# STM.net
KiCad netlist of a schematic drawn in Altium Designer
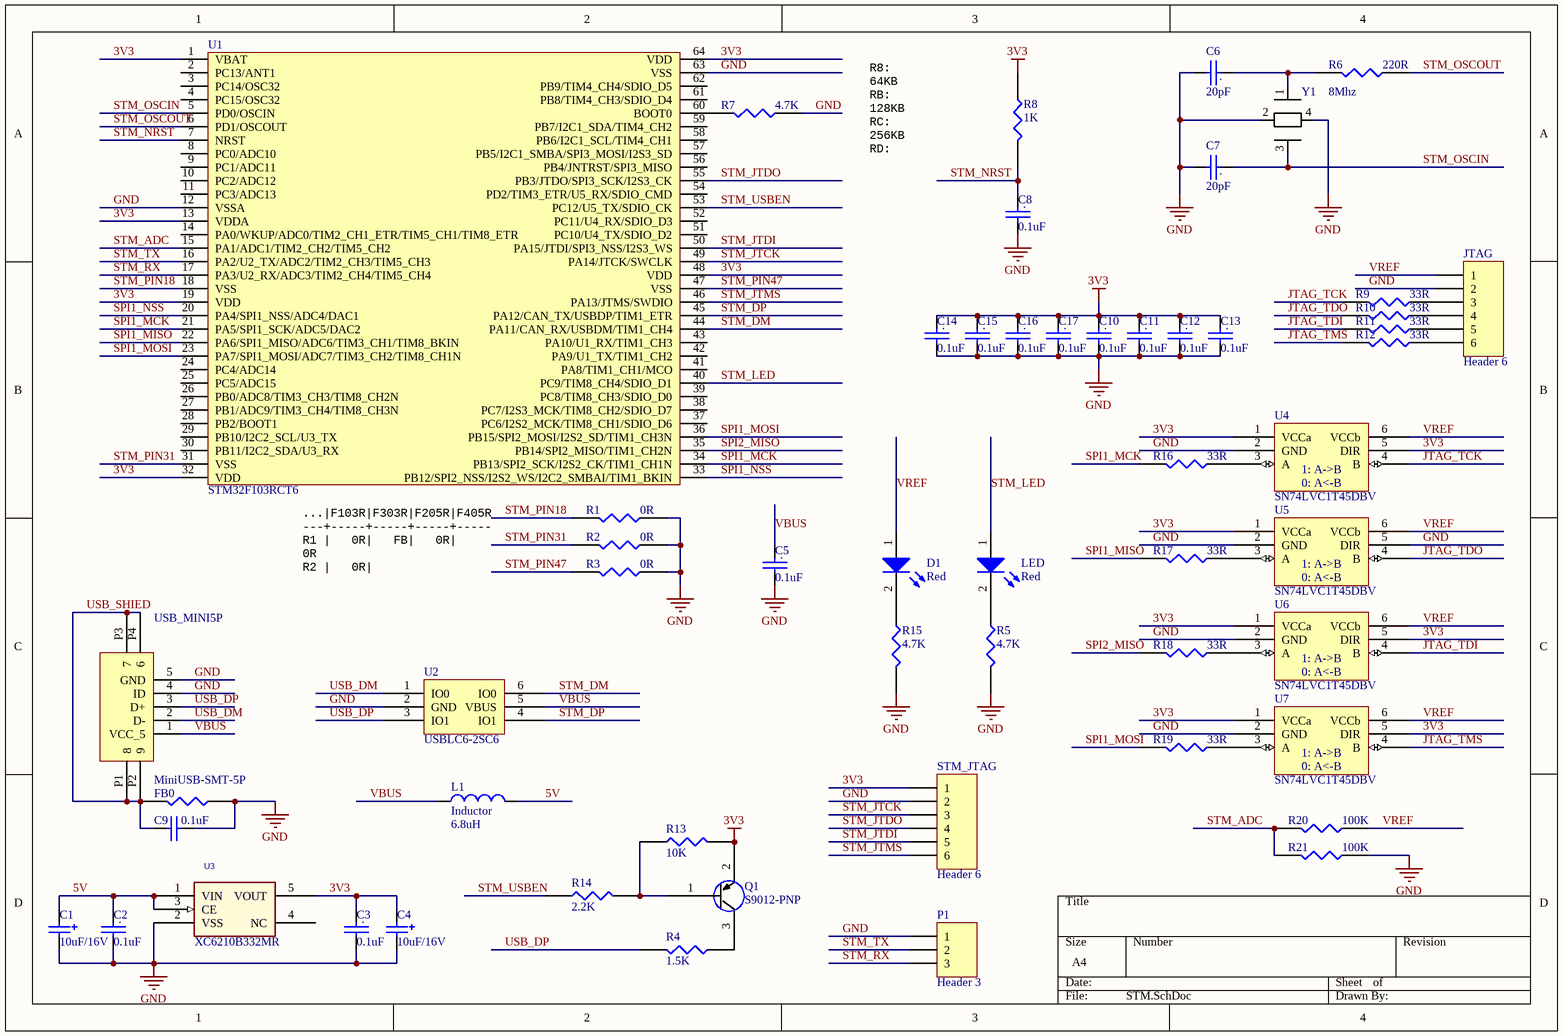
[diagram p0: STM.SchDoc]

(export (version "E")
  (design (tool "Eeschema 10.0.6"))
  (components
    (comp (ref "C1")
      (value "10uF/16V")
      (footprint "C1206")
      (description "Polarized Capacitor (Surface Mount)")
      (fields (field (name "Comment") "CAP") (field (name "PUBLISHER") "Altium Limited"))
      (libsource (lib "R-C-L-D") (part "CAP Polarity"))
    )
    (comp (ref "C2")
      (value "0.1uF")
      (footprint "C0603")
      (description "Capacitor")
      (fields (field (name "Comment") "CAP Ceramics"))
      (libsource (lib "R-C-L-D") (part "CAP Ceramics"))
    )
    (comp (ref "C3")
      (value "0.1uF")
      (footprint "C0603")
      (description "Capacitor")
      (fields (field (name "Comment") "CAP Ceramics"))
      (libsource (lib "R-C-L-D") (part "CAP Ceramics"))
    )
    (comp (ref "C4")
      (value "10uF/16V")
      (footprint "C1206")
      (description "Polarized Capacitor (Surface Mount)")
      (fields (field (name "Comment") "CAP") (field (name "PUBLISHER") "Altium Limited"))
      (libsource (lib "R-C-L-D") (part "CAP Polarity"))
    )
    (comp (ref "C5")
      (value "0.1uF")
      (footprint "C0603")
      (description "Capacitor")
      (fields (field (name "Comment") "CAP Ceramics"))
      (libsource (lib "R-C-L-D") (part "CAP Ceramics"))
    )
    (comp (ref "C6")
      (value "20pF")
      (footprint "C0603")
      (description "Capacitor")
      (fields (field (name "Comment") "CAP Ceramics"))
      (libsource (lib "R-C-L-D") (part "CAP Ceramics"))
    )
    (comp (ref "C7")
      (value "20pF")
      (footprint "C0603")
      (description "Capacitor")
      (fields (field (name "Comment") "CAP Ceramics"))
      (libsource (lib "R-C-L-D") (part "CAP Ceramics"))
    )
    (comp (ref "C8")
      (value "0.1uF")
      (footprint "C0603")
      (description "Capacitor")
      (fields (field (name "Comment") "CAP Ceramics"))
      (libsource (lib "R-C-L-D") (part "CAP Ceramics"))
    )
    (comp (ref "C9")
      (value "0.1uF")
      (footprint "C0603")
      (description "Capacitor")
      (fields (field (name "Comment") "CAP Ceramics"))
      (libsource (lib "R-C-L-D") (part "CAP Ceramics"))
    )
    (comp (ref "C10")
      (value "0.1uF")
      (footprint "C0603")
      (description "Capacitor")
      (fields (field (name "Comment") "CAP Ceramics"))
      (libsource (lib "R-C-L-D") (part "CAP Ceramics"))
    )
    (comp (ref "C11")
      (value "0.1uF")
      (footprint "C0603")
      (description "Capacitor")
      (fields (field (name "Comment") "CAP Ceramics"))
      (libsource (lib "R-C-L-D") (part "CAP Ceramics"))
    )
    (comp (ref "C12")
      (value "0.1uF")
      (footprint "C0603")
      (description "Capacitor")
      (fields (field (name "Comment") "CAP Ceramics"))
      (libsource (lib "R-C-L-D") (part "CAP Ceramics"))
    )
    (comp (ref "C13")
      (value "0.1uF")
      (footprint "C0603")
      (description "Capacitor")
      (fields (field (name "Comment") "CAP Ceramics"))
      (libsource (lib "R-C-L-D") (part "CAP Ceramics"))
    )
    (comp (ref "C14")
      (value "0.1uF")
      (footprint "C0603")
      (description "Capacitor")
      (fields (field (name "Comment") "CAP Ceramics"))
      (libsource (lib "R-C-L-D") (part "CAP Ceramics"))
    )
    (comp (ref "C15")
      (value "0.1uF")
      (footprint "C0603")
      (description "Capacitor")
      (fields (field (name "Comment") "CAP Ceramics"))
      (libsource (lib "R-C-L-D") (part "CAP Ceramics"))
    )
    (comp (ref "C16")
      (value "0.1uF")
      (footprint "C0603")
      (description "Capacitor")
      (fields (field (name "Comment") "CAP Ceramics"))
      (libsource (lib "R-C-L-D") (part "CAP Ceramics"))
    )
    (comp (ref "C17")
      (value "0.1uF")
      (footprint "C0603")
      (description "Capacitor")
      (fields (field (name "Comment") "CAP Ceramics"))
      (libsource (lib "R-C-L-D") (part "CAP Ceramics"))
    )
    (comp (ref "D1")
      (value "Red")
      (footprint "D0603")
      (description "LED")
      (fields (field (name "PUBLISHER") "Altium Limited"))
      (libsource (lib "R-C-L-D") (part "LED"))
    )
    (comp (ref "FB0")
      (value "RES")
      (footprint "R0603")
      (description "Res")
      (libsource (lib "R-C-L-D") (part "RES"))
    )
    (comp (ref "JTAG")
      (value "Header 6")
      (footprint "HDR1X6")
      (description "Header, 6-Pin")
      (fields (field (name "PUBLISHER") "Altium Limited"))
      (libsource (lib "Miscellaneous Connectors") (part "Header 6"))
    )
    (comp (ref "L1")
      (value "Inductor")
      (footprint "L1206")
      (fields (field (name "ALTIUM_VALUE") "6.8uH") (field (name "PUBLISHER") "Altium Limited"))
      (libsource (lib "R-C-L-D") (part "Inductor"))
    )
    (comp (ref "LED")
      (value "Red")
      (footprint "D0603")
      (description "LED")
      (fields (field (name "PUBLISHER") "Altium Limited"))
      (libsource (lib "R-C-L-D") (part "LED"))
    )
    (comp (ref "P1")
      (value "Header 3")
      (footprint "HDR1X3")
      (description "Header, 3-Pin")
      (fields (field (name "PUBLISHER") "Altium Limited"))
      (libsource (lib "Miscellaneous Connectors") (part "Header 3"))
    )
    (comp (ref "Q1")
      (value "S9012-PNP")
      (footprint "SOT23-3")
      (description "S9012-PNP-SOT23")
      (libsource (lib "S9012-PNP-SOT23") (part "S9012"))
    )
    (comp (ref "R1")
      (value "0R")
      (footprint "R0603")
      (description "Res")
      (libsource (lib "R-C-L-D") (part "RES"))
    )
    (comp (ref "R2")
      (value "0R")
      (footprint "R0603")
      (description "Res")
      (libsource (lib "R-C-L-D") (part "RES"))
    )
    (comp (ref "R3")
      (value "0R")
      (footprint "R0603")
      (description "Res")
      (libsource (lib "R-C-L-D") (part "RES"))
    )
    (comp (ref "R4")
      (value "1.5K")
      (footprint "R0603")
      (description "Res")
      (fields (field (name "Comment") "RES"))
      (libsource (lib "R-C-L-D") (part "RES"))
    )
    (comp (ref "R5")
      (value "4.7K")
      (footprint "R0603")
      (description "Res")
      (libsource (lib "R-C-L-D") (part "RES"))
    )
    (comp (ref "R6")
      (value "220R")
      (footprint "R0603")
      (description "Res")
      (libsource (lib "R-C-L-D") (part "RES"))
    )
    (comp (ref "R7")
      (value "4.7K")
      (footprint "R0603")
      (description "Res")
      (libsource (lib "R-C-L-D") (part "RES"))
    )
    (comp (ref "R8")
      (value "1K")
      (footprint "R0603")
      (description "Res")
      (libsource (lib "R-C-L-D") (part "RES"))
    )
    (comp (ref "R9")
      (value "33R")
      (footprint "R0603")
      (description "Res")
      (fields (field (name "Comment") "RES"))
      (libsource (lib "R-C-L-D") (part "RES"))
    )
    (comp (ref "R10")
      (value "33R")
      (footprint "R0603")
      (description "Res")
      (fields (field (name "Comment") "RES"))
      (libsource (lib "R-C-L-D") (part "RES"))
    )
    (comp (ref "R11")
      (value "33R")
      (footprint "R0603")
      (description "Res")
      (fields (field (name "Comment") "RES"))
      (libsource (lib "R-C-L-D") (part "RES"))
    )
    (comp (ref "R12")
      (value "33R")
      (footprint "R0603")
      (description "Res")
      (fields (field (name "Comment") "RES"))
      (libsource (lib "R-C-L-D") (part "RES"))
    )
    (comp (ref "R13")
      (value "10K")
      (footprint "R0603")
      (description "Res")
      (fields (field (name "Comment") "RES"))
      (libsource (lib "R-C-L-D") (part "RES"))
    )
    (comp (ref "R14")
      (value "2.2K")
      (footprint "R0603")
      (description "Res")
      (fields (field (name "Comment") "RES"))
      (libsource (lib "R-C-L-D") (part "RES"))
    )
    (comp (ref "R15")
      (value "4.7K")
      (footprint "R0603")
      (description "Res")
      (libsource (lib "R-C-L-D") (part "RES"))
    )
    (comp (ref "R16")
      (value "33R")
      (footprint "R0603")
      (description "Res")
      (fields (field (name "Comment") "RES"))
      (libsource (lib "R-C-L-D") (part "RES"))
    )
    (comp (ref "R17")
      (value "33R")
      (footprint "R0603")
      (description "Res")
      (fields (field (name "Comment") "RES"))
      (libsource (lib "R-C-L-D") (part "RES"))
    )
    (comp (ref "R18")
      (value "33R")
      (footprint "R0603")
      (description "Res")
      (fields (field (name "Comment") "RES"))
      (libsource (lib "R-C-L-D") (part "RES"))
    )
    (comp (ref "R19")
      (value "33R")
      (footprint "R0603")
      (description "Res")
      (fields (field (name "Comment") "RES"))
      (libsource (lib "R-C-L-D") (part "RES"))
    )
    (comp (ref "R20")
      (value "100K")
      (footprint "R0603")
      (description "Res")
      (libsource (lib "R-C-L-D") (part "RES"))
    )
    (comp (ref "R21")
      (value "100K")
      (footprint "R0603")
      (description "Res")
      (libsource (lib "R-C-L-D") (part "RES"))
    )
    (comp (ref "STM_JTAG")
      (value "Header 6")
      (footprint "HDR1X6")
      (description "Header, 6-Pin")
      (fields (field (name "PUBLISHER") "Altium Limited"))
      (libsource (lib "Miscellaneous Connectors") (part "Header 6"))
    )
    (comp (ref "U1")
      (value "STM32F103RCT6")
      (footprint "LQFP64_DE12_e0.5_PAD1.8x0.3_offset2.3_mm")
      (description "ST STM32 Cortex-M3")
      (libsource (lib "STM32F103R") (part "STM32F103R"))
    )
    (comp (ref "U2")
      (value "USBLC6-2SC6")
      (footprint "SOT23-6")
      (description "USB EMI ESD Protect")
      (libsource (lib "USBLC6-2") (part "USBLC6-2"))
    )
    (comp (ref "U3")
      (value "XC6210B332MR")
      (footprint "SOT23-5")
      (description "5V->3.3V")
      (fields (field (name "Comment") "LDO"))
      (libsource (lib "LDO") (part "XC6210B-3.3"))
    )
    (comp (ref "U4")
      (value "SN74LVC1T45DBV")
      (footprint "SOT23-6")
      (description "TI SN74LVC1T45")
      (libsource (lib "SN74LVC1T45") (part "SN74LVC1T45"))
    )
    (comp (ref "U5")
      (value "SN74LVC1T45DBV")
      (footprint "SOT23-6")
      (description "TI SN74LVC1T45")
      (libsource (lib "SN74LVC1T45") (part "SN74LVC1T45"))
    )
    (comp (ref "U6")
      (value "SN74LVC1T45DBV")
      (footprint "SOT23-6")
      (description "TI SN74LVC1T45")
      (libsource (lib "SN74LVC1T45") (part "SN74LVC1T45"))
    )
    (comp (ref "U7")
      (value "SN74LVC1T45DBV")
      (footprint "SOT23-6")
      (description "TI SN74LVC1T45")
      (libsource (lib "SN74LVC1T45") (part "SN74LVC1T45"))
    )
    (comp (ref "USB_MINI5P")
      (value "MiniUSB-SMT-5P")
      (footprint "USB_MINI")
      (description "MiniUSB SMT")
      (libsource (lib "MiniUSB-5P") (part "MiniUSB_5P"))
    )
    (comp (ref "Y1")
      (value "8Mhz")
      (footprint "SMD3225")
      (description "Crystal")
      (libsource (lib "Crystal") (part "CRY"))
    )
  )
  (nets
    (net (code "1") (name "/5V") (class "Default")
      (node (ref "C1") (pin "1") (pinfunction "1_1") (pintype "passive"))
      (node (ref "C2") (pin "1") (pinfunction "1_1") (pintype "passive"))
      (node (ref "L1") (pin "2") (pinfunction "2_2") (pintype "passive"))
      (node (ref "U3") (pin "1") (pinfunction "VIN_1") (pintype "power_in"))
      (node (ref "U3") (pin "3") (pinfunction "CE_3") (pintype "input"))
    )
    (net (code "2") (name "/JTAG_TCK") (class "Default")
      (node (ref "R9") (pin "2") (pinfunction "2_2") (pintype "passive"))
      (node (ref "U4") (pin "4") (pinfunction "B_4") (pintype "bidirectional"))
    )
    (net (code "3") (name "/JTAG_TDI") (class "Default")
      (node (ref "R11") (pin "2") (pinfunction "2_2") (pintype "passive"))
      (node (ref "U6") (pin "4") (pinfunction "B_4") (pintype "bidirectional"))
    )
    (net (code "4") (name "/JTAG_TDO") (class "Default")
      (node (ref "R10") (pin "2") (pinfunction "2_2") (pintype "passive"))
      (node (ref "U5") (pin "4") (pinfunction "B_4") (pintype "bidirectional"))
    )
    (net (code "5") (name "/JTAG_TMS") (class "Default")
      (node (ref "R12") (pin "2") (pinfunction "2_2") (pintype "passive"))
      (node (ref "U7") (pin "4") (pinfunction "B_4") (pintype "bidirectional"))
    )
    (net (code "6") (name "/SPI1_MCK") (class "Default")
      (node (ref "R16") (pin "2") (pinfunction "2_2") (pintype "passive"))
      (node (ref "U1") (pin "21") (pinfunction "PA5/SPI1_SCK/ADC5/DAC2_21") (pintype "passive"))
      (node (ref "U1") (pin "34") (pinfunction "PB13/SPI2_SCK/I2S2_CK/TIM1_CH1N_34") (pintype "passive"))
    )
    (net (code "7") (name "/SPI1_MISO") (class "Default")
      (node (ref "R17") (pin "2") (pinfunction "2_2") (pintype "passive"))
      (node (ref "U1") (pin "22") (pinfunction "PA6/SPI1_MISO/ADC6/TIM3_CH1/TIM8_BKIN_22") (pintype "passive"))
    )
    (net (code "8") (name "/SPI1_MOSI") (class "Default")
      (node (ref "R19") (pin "2") (pinfunction "2_2") (pintype "passive"))
      (node (ref "U1") (pin "23") (pinfunction "PA7/SPI1_MOSI/ADC7/TIM3_CH2/TIM8_CH1N_23") (pintype "passive"))
      (node (ref "U1") (pin "36") (pinfunction "PB15/SPI2_MOSI/I2S2_SD/TIM1_CH3N_36") (pintype "passive"))
    )
    (net (code "9") (name "/SPI1_NSS") (class "Default")
      (node (ref "U1") (pin "20") (pinfunction "PA4/SPI1_NSS/ADC4/DAC1_20") (pintype "passive"))
      (node (ref "U1") (pin "33") (pinfunction "PB12/SPI2_NSS/I2S2_WS/I2C2_SMBAI/TIM1_BKIN_33") (pintype "passive"))
    )
    (net (code "10") (name "/SPI2_MISO") (class "Default")
      (node (ref "R18") (pin "2") (pinfunction "2_2") (pintype "passive"))
      (node (ref "U1") (pin "35") (pinfunction "PB14/SPI2_MISO/TIM1_CH2N_35") (pintype "passive"))
    )
    (net (code "11") (name "/STM_ADC") (class "Default")
      (node (ref "R20") (pin "2") (pinfunction "2_2") (pintype "passive"))
      (node (ref "R21") (pin "2") (pinfunction "2_2") (pintype "passive"))
      (node (ref "U1") (pin "15") (pinfunction "PA1/ADC1/TIM2_CH2/TIM5_CH2_15") (pintype "passive"))
    )
    (net (code "12") (name "/STM_DM") (class "Default")
      (node (ref "U1") (pin "44") (pinfunction "PA11/CAN_RX/USBDM/TIM1_CH4_44") (pintype "passive"))
      (node (ref "U2") (pin "6") (pinfunction "IO0_6") (pintype "passive"))
    )
    (net (code "13") (name "/STM_DP") (class "Default")
      (node (ref "U1") (pin "45") (pinfunction "PA12/CAN_TX/USBDP/TIM1_ETR_45") (pintype "passive"))
      (node (ref "U2") (pin "4") (pinfunction "IO1_4") (pintype "passive"))
    )
    (net (code "14") (name "/STM_JTCK") (class "Default")
      (node (ref "STM_JTAG") (pin "3") (pinfunction "3_3") (pintype "passive"))
      (node (ref "U1") (pin "49") (pinfunction "PA14/JTCK/SWCLK_49") (pintype "passive"))
    )
    (net (code "15") (name "/STM_JTDI") (class "Default")
      (node (ref "STM_JTAG") (pin "5") (pinfunction "5_5") (pintype "passive"))
      (node (ref "U1") (pin "50") (pinfunction "PA15/JTDI/SPI3_NSS/I2S3_WS_50") (pintype "passive"))
    )
    (net (code "16") (name "/STM_JTDO") (class "Default")
      (node (ref "STM_JTAG") (pin "4") (pinfunction "4_4") (pintype "passive"))
      (node (ref "U1") (pin "55") (pinfunction "PB3/JTDO/SPI3_SCK/I2S3_CK_55") (pintype "passive"))
    )
    (net (code "17") (name "/STM_JTMS") (class "Default")
      (node (ref "STM_JTAG") (pin "6") (pinfunction "6_6") (pintype "passive"))
      (node (ref "U1") (pin "46") (pinfunction "PA13/JTMS/SWDIO_46") (pintype "passive"))
    )
    (net (code "18") (name "/STM_LED") (class "Default")
      (node (ref "LED") (pin "1") (pinfunction "A_1") (pintype "passive"))
      (node (ref "U1") (pin "40") (pinfunction "PC9/TIM8_CH4/SDIO_D1_40") (pintype "passive"))
    )
    (net (code "19") (name "/STM_NRST") (class "Default")
      (node (ref "C8") (pin "1") (pinfunction "1_1") (pintype "passive"))
      (node (ref "R8") (pin "2") (pinfunction "2_2") (pintype "passive"))
      (node (ref "U1") (pin "7") (pinfunction "NRST_7") (pintype "passive"))
    )
    (net (code "20") (name "/STM_OSCIN") (class "Default")
      (node (ref "C7") (pin "1") (pinfunction "1_1") (pintype "passive"))
      (node (ref "U1") (pin "5") (pinfunction "PD0/OSCIN_5") (pintype "passive"))
      (node (ref "Y1") (pin "3") (pinfunction "3_3") (pintype "passive"))
    )
    (net (code "21") (name "/STM_OSCOUT") (class "Default")
      (node (ref "R6") (pin "1") (pinfunction "1_1") (pintype "passive"))
      (node (ref "U1") (pin "6") (pinfunction "PD1/OSCOUT_6") (pintype "passive"))
    )
    (net (code "22") (name "/STM_PIN18") (class "Default")
      (node (ref "R1") (pin "2") (pinfunction "2_2") (pintype "passive"))
      (node (ref "U1") (pin "18") (pinfunction "VSS_18") (pintype "passive"))
    )
    (net (code "23") (name "/STM_PIN31") (class "Default")
      (node (ref "R2") (pin "2") (pinfunction "2_2") (pintype "passive"))
      (node (ref "U1") (pin "31") (pinfunction "VSS_31") (pintype "passive"))
    )
    (net (code "24") (name "/STM_PIN47") (class "Default")
      (node (ref "R3") (pin "2") (pinfunction "2_2") (pintype "passive"))
      (node (ref "U1") (pin "47") (pinfunction "VSS_47") (pintype "passive"))
    )
    (net (code "25") (name "/STM_RX") (class "Default")
      (node (ref "P1") (pin "3") (pinfunction "3_3") (pintype "passive"))
      (node (ref "U1") (pin "17") (pinfunction "PA3/U2_RX/ADC3/TIM2_CH4/TIM5_CH4_17") (pintype "passive"))
    )
    (net (code "26") (name "/STM_TX") (class "Default")
      (node (ref "P1") (pin "2") (pinfunction "2_2") (pintype "passive"))
      (node (ref "U1") (pin "16") (pinfunction "PA2/U2_TX/ADC2/TIM2_CH3/TIM5_CH3_16") (pintype "passive"))
    )
    (net (code "27") (name "/STM_USBEN") (class "Default")
      (node (ref "R14") (pin "1") (pinfunction "1_1") (pintype "passive"))
      (node (ref "U1") (pin "53") (pinfunction "PC12/U5_TX/SDIO_CK_53") (pintype "passive"))
    )
    (net (code "28") (name "/USB_DM") (class "Default")
      (node (ref "U2") (pin "1") (pinfunction "IO0_1") (pintype "passive"))
      (node (ref "USB_MINI5P") (pin "2") (pinfunction "D-_2") (pintype "passive"))
    )
    (net (code "29") (name "/USB_DP") (class "Default")
      (node (ref "R4") (pin "2") (pinfunction "2_2") (pintype "passive"))
      (node (ref "U2") (pin "3") (pinfunction "IO1_3") (pintype "passive"))
      (node (ref "USB_MINI5P") (pin "3") (pinfunction "D+_3") (pintype "passive"))
    )
    (net (code "30") (name "/USB_SHIED") (class "Default")
      (node (ref "C9") (pin "1") (pinfunction "1_1") (pintype "passive"))
      (node (ref "FB0") (pin "2") (pinfunction "2_2") (pintype "passive"))
      (node (ref "USB_MINI5P") (pin "P1") (pinfunction "8_P1") (pintype "passive"))
      (node (ref "USB_MINI5P") (pin "P2") (pinfunction "9_P2") (pintype "passive"))
      (node (ref "USB_MINI5P") (pin "P3") (pinfunction "7_P3") (pintype "passive"))
      (node (ref "USB_MINI5P") (pin "P4") (pinfunction "6_P4") (pintype "passive"))
    )
    (net (code "31") (name "/VBUS") (class "Default")
      (node (ref "C5") (pin "1") (pinfunction "1_1") (pintype "passive"))
      (node (ref "L1") (pin "1") (pinfunction "1_1") (pintype "passive"))
      (node (ref "U2") (pin "5") (pinfunction "VBUS_5") (pintype "passive"))
      (node (ref "USB_MINI5P") (pin "1") (pinfunction "VCC_5_1") (pintype "passive"))
    )
    (net (code "32") (name "/VREF") (class "Default")
      (node (ref "D1") (pin "1") (pinfunction "A_1") (pintype "passive"))
      (node (ref "JTAG") (pin "1") (pinfunction "1_1") (pintype "passive"))
      (node (ref "R20") (pin "1") (pinfunction "1_1") (pintype "passive"))
      (node (ref "U4") (pin "6") (pinfunction "VCCb_6") (pintype "passive"))
      (node (ref "U5") (pin "6") (pinfunction "VCCb_6") (pintype "passive"))
      (node (ref "U6") (pin "6") (pinfunction "VCCb_6") (pintype "passive"))
      (node (ref "U7") (pin "6") (pinfunction "VCCb_6") (pintype "passive"))
    )
    (net (code "33") (name "3V3") (class "Default")
      (node (ref "C10") (pin "1") (pinfunction "1_1") (pintype "passive"))
      (node (ref "C11") (pin "1") (pinfunction "1_1") (pintype "passive"))
      (node (ref "C12") (pin "1") (pinfunction "1_1") (pintype "passive"))
      (node (ref "C13") (pin "1") (pinfunction "1_1") (pintype "passive"))
      (node (ref "C14") (pin "1") (pinfunction "1_1") (pintype "passive"))
      (node (ref "C15") (pin "1") (pinfunction "1_1") (pintype "passive"))
      (node (ref "C16") (pin "1") (pinfunction "1_1") (pintype "passive"))
      (node (ref "C17") (pin "1") (pinfunction "1_1") (pintype "passive"))
      (node (ref "C3") (pin "1") (pinfunction "1_1") (pintype "passive"))
      (node (ref "C4") (pin "1") (pinfunction "1_1") (pintype "passive"))
      (node (ref "Q1") (pin "2") (pinfunction "e_2") (pintype "passive"))
      (node (ref "R13") (pin "2") (pinfunction "2_2") (pintype "passive"))
      (node (ref "R8") (pin "1") (pinfunction "1_1") (pintype "passive"))
      (node (ref "STM_JTAG") (pin "1") (pinfunction "1_1") (pintype "passive"))
      (node (ref "U1") (pin "1") (pinfunction "VBAT_1") (pintype "passive"))
      (node (ref "U1") (pin "13") (pinfunction "VDDA_13") (pintype "passive"))
      (node (ref "U1") (pin "19") (pinfunction "VDD_19") (pintype "passive"))
      (node (ref "U1") (pin "32") (pinfunction "VDD_32") (pintype "passive"))
      (node (ref "U1") (pin "48") (pinfunction "VDD_48") (pintype "passive"))
      (node (ref "U1") (pin "64") (pinfunction "VDD_64") (pintype "passive"))
      (node (ref "U3") (pin "5") (pinfunction "VOUT_5") (pintype "passive"))
      (node (ref "U4") (pin "1") (pinfunction "VCCa_1") (pintype "passive"))
      (node (ref "U4") (pin "5") (pinfunction "DIR_5") (pintype "passive"))
      (node (ref "U5") (pin "1") (pinfunction "VCCa_1") (pintype "passive"))
      (node (ref "U6") (pin "1") (pinfunction "VCCa_1") (pintype "passive"))
      (node (ref "U6") (pin "5") (pinfunction "DIR_5") (pintype "passive"))
      (node (ref "U7") (pin "1") (pinfunction "VCCa_1") (pintype "passive"))
      (node (ref "U7") (pin "5") (pinfunction "DIR_5") (pintype "passive"))
    )
    (net (code "34") (name "GND") (class "Default")
      (node (ref "C1") (pin "2") (pinfunction "2_2") (pintype "passive"))
      (node (ref "C10") (pin "2") (pinfunction "2_2") (pintype "passive"))
      (node (ref "C11") (pin "2") (pinfunction "2_2") (pintype "passive"))
      (node (ref "C12") (pin "2") (pinfunction "2_2") (pintype "passive"))
      (node (ref "C13") (pin "2") (pinfunction "2_2") (pintype "passive"))
      (node (ref "C14") (pin "2") (pinfunction "2_2") (pintype "passive"))
      (node (ref "C15") (pin "2") (pinfunction "2_2") (pintype "passive"))
      (node (ref "C16") (pin "2") (pinfunction "2_2") (pintype "passive"))
      (node (ref "C17") (pin "2") (pinfunction "2_2") (pintype "passive"))
      (node (ref "C2") (pin "2") (pinfunction "2_2") (pintype "passive"))
      (node (ref "C3") (pin "2") (pinfunction "2_2") (pintype "passive"))
      (node (ref "C4") (pin "2") (pinfunction "2_2") (pintype "passive"))
      (node (ref "C5") (pin "2") (pinfunction "2_2") (pintype "passive"))
      (node (ref "C6") (pin "2") (pinfunction "2_2") (pintype "passive"))
      (node (ref "C7") (pin "2") (pinfunction "2_2") (pintype "passive"))
      (node (ref "C8") (pin "2") (pinfunction "2_2") (pintype "passive"))
      (node (ref "C9") (pin "2") (pinfunction "2_2") (pintype "passive"))
      (node (ref "FB0") (pin "1") (pinfunction "1_1") (pintype "passive"))
      (node (ref "JTAG") (pin "2") (pinfunction "2_2") (pintype "passive"))
      (node (ref "P1") (pin "1") (pinfunction "1_1") (pintype "passive"))
      (node (ref "R1") (pin "1") (pinfunction "1_1") (pintype "passive"))
      (node (ref "R15") (pin "2") (pinfunction "2_2") (pintype "passive"))
      (node (ref "R2") (pin "1") (pinfunction "1_1") (pintype "passive"))
      (node (ref "R21") (pin "1") (pinfunction "1_1") (pintype "passive"))
      (node (ref "R3") (pin "1") (pinfunction "1_1") (pintype "passive"))
      (node (ref "R5") (pin "2") (pinfunction "2_2") (pintype "passive"))
      (node (ref "R7") (pin "1") (pinfunction "1_1") (pintype "passive"))
      (node (ref "STM_JTAG") (pin "2") (pinfunction "2_2") (pintype "passive"))
      (node (ref "U1") (pin "12") (pinfunction "VSSA_12") (pintype "passive"))
      (node (ref "U1") (pin "63") (pinfunction "VSS_63") (pintype "passive"))
      (node (ref "U2") (pin "2") (pinfunction "GND_2") (pintype "passive"))
      (node (ref "U3") (pin "2") (pinfunction "VSS_2") (pintype "power_in"))
      (node (ref "U4") (pin "2") (pinfunction "GND_2") (pintype "passive"))
      (node (ref "U5") (pin "2") (pinfunction "GND_2") (pintype "passive"))
      (node (ref "U5") (pin "5") (pinfunction "DIR_5") (pintype "passive"))
      (node (ref "U6") (pin "2") (pinfunction "GND_2") (pintype "passive"))
      (node (ref "U7") (pin "2") (pinfunction "GND_2") (pintype "passive"))
      (node (ref "USB_MINI5P") (pin "4") (pinfunction "ID_4") (pintype "passive"))
      (node (ref "USB_MINI5P") (pin "5") (pinfunction "GND_5") (pintype "passive"))
      (node (ref "Y1") (pin "2") (pinfunction "2_2") (pintype "passive"))
      (node (ref "Y1") (pin "4") (pinfunction "4_4") (pintype "passive"))
    )
    (net (code "35") (name "Net-(C6-Pad1)") (class "Default")
      (node (ref "C6") (pin "1") (pinfunction "1_1") (pintype "passive"))
      (node (ref "R6") (pin "2") (pinfunction "2_2") (pintype "passive"))
      (node (ref "Y1") (pin "1") (pinfunction "1_1") (pintype "passive"))
    )
    (net (code "36") (name "Net-(D1-K)") (class "Default")
      (node (ref "D1") (pin "2") (pinfunction "K_2") (pintype "passive"))
      (node (ref "R15") (pin "1") (pinfunction "1_1") (pintype "passive"))
    )
    (net (code "37") (name "Net-(JTAG-Pad3)") (class "Default")
      (node (ref "JTAG") (pin "3") (pinfunction "3_3") (pintype "passive"))
      (node (ref "R9") (pin "1") (pinfunction "1_1") (pintype "passive"))
    )
    (net (code "38") (name "Net-(JTAG-Pad4)") (class "Default")
      (node (ref "JTAG") (pin "4") (pinfunction "4_4") (pintype "passive"))
      (node (ref "R10") (pin "1") (pinfunction "1_1") (pintype "passive"))
    )
    (net (code "39") (name "Net-(JTAG-Pad5)") (class "Default")
      (node (ref "JTAG") (pin "5") (pinfunction "5_5") (pintype "passive"))
      (node (ref "R11") (pin "1") (pinfunction "1_1") (pintype "passive"))
    )
    (net (code "40") (name "Net-(JTAG-Pad6)") (class "Default")
      (node (ref "JTAG") (pin "6") (pinfunction "6_6") (pintype "passive"))
      (node (ref "R12") (pin "1") (pinfunction "1_1") (pintype "passive"))
    )
    (net (code "41") (name "Net-(LED-K)") (class "Default")
      (node (ref "LED") (pin "2") (pinfunction "K_2") (pintype "passive"))
      (node (ref "R5") (pin "1") (pinfunction "1_1") (pintype "passive"))
    )
    (net (code "42") (name "Net-(Q1-b)") (class "Default")
      (node (ref "Q1") (pin "1") (pinfunction "b_1") (pintype "passive"))
      (node (ref "R13") (pin "1") (pinfunction "1_1") (pintype "passive"))
      (node (ref "R14") (pin "2") (pinfunction "2_2") (pintype "passive"))
    )
    (net (code "43") (name "Net-(Q1-c)") (class "Default")
      (node (ref "Q1") (pin "3") (pinfunction "c_3") (pintype "passive"))
      (node (ref "R4") (pin "1") (pinfunction "1_1") (pintype "passive"))
    )
    (net (code "44") (name "Net-(U1-BOOT0)") (class "Default")
      (node (ref "R7") (pin "2") (pinfunction "2_2") (pintype "passive"))
      (node (ref "U1") (pin "60") (pinfunction "BOOT0_60") (pintype "passive"))
    )
    (net (code "45") (name "Net-(U4-A)") (class "Default")
      (node (ref "R16") (pin "1") (pinfunction "1_1") (pintype "passive"))
      (node (ref "U4") (pin "3") (pinfunction "A_3") (pintype "bidirectional"))
    )
    (net (code "46") (name "Net-(U5-A)") (class "Default")
      (node (ref "R17") (pin "1") (pinfunction "1_1") (pintype "passive"))
      (node (ref "U5") (pin "3") (pinfunction "A_3") (pintype "bidirectional"))
    )
    (net (code "47") (name "Net-(U6-A)") (class "Default")
      (node (ref "R18") (pin "1") (pinfunction "1_1") (pintype "passive"))
      (node (ref "U6") (pin "3") (pinfunction "A_3") (pintype "bidirectional"))
    )
    (net (code "48") (name "Net-(U7-A)") (class "Default")
      (node (ref "R19") (pin "1") (pinfunction "1_1") (pintype "passive"))
      (node (ref "U7") (pin "3") (pinfunction "A_3") (pintype "bidirectional"))
    )
    (net (code "49") (name "unconnected-(U1-PA0{slash}WKUP{slash}ADC0{slash}TIM2_CH1_ETR{slash}TIM5_CH1{slash}TIM8_ETR-Pad14)") (class "Default")
      (node (ref "U1") (pin "14") (pinfunction "PA0/WKUP/ADC0/TIM2_CH1_ETR/TIM5_CH1/TIM8_ETR_14") (pintype "passive"))
    )
    (net (code "50") (name "unconnected-(U1-PA8{slash}TIM1_CH1{slash}MCO-Pad41)") (class "Default")
      (node (ref "U1") (pin "41") (pinfunction "PA8/TIM1_CH1/MCO_41") (pintype "passive"))
    )
    (net (code "51") (name "unconnected-(U1-PA9{slash}U1_TX{slash}TIM1_CH2-Pad42)") (class "Default")
      (node (ref "U1") (pin "42") (pinfunction "PA9/U1_TX/TIM1_CH2_42") (pintype "passive"))
    )
    (net (code "52") (name "unconnected-(U1-PA10{slash}U1_RX{slash}TIM1_CH3-Pad43)") (class "Default")
      (node (ref "U1") (pin "43") (pinfunction "PA10/U1_RX/TIM1_CH3_43") (pintype "passive"))
    )
    (net (code "53") (name "unconnected-(U1-PB0{slash}ADC8{slash}TIM3_CH3{slash}TIM8_CH2N-Pad26)") (class "Default")
      (node (ref "U1") (pin "26") (pinfunction "PB0/ADC8/TIM3_CH3/TIM8_CH2N_26") (pintype "passive"))
    )
    (net (code "54") (name "unconnected-(U1-PB1{slash}ADC9{slash}TIM3_CH4{slash}TIM8_CH3N-Pad27)") (class "Default")
      (node (ref "U1") (pin "27") (pinfunction "PB1/ADC9/TIM3_CH4/TIM8_CH3N_27") (pintype "passive"))
    )
    (net (code "55") (name "unconnected-(U1-PB2{slash}BOOT1-Pad28)") (class "Default")
      (node (ref "U1") (pin "28") (pinfunction "PB2/BOOT1_28") (pintype "passive"))
    )
    (net (code "56") (name "unconnected-(U1-PB4{slash}JNTRST{slash}SPI3_MISO-Pad56)") (class "Default")
      (node (ref "U1") (pin "56") (pinfunction "PB4/JNTRST/SPI3_MISO_56") (pintype "passive"))
    )
    (net (code "57") (name "unconnected-(U1-PB5{slash}I2C1_SMBA{slash}SPI3_MOSI{slash}I2S3_SD-Pad57)") (class "Default")
      (node (ref "U1") (pin "57") (pinfunction "PB5/I2C1_SMBA/SPI3_MOSI/I2S3_SD_57") (pintype "passive"))
    )
    (net (code "58") (name "unconnected-(U1-PB6{slash}I2C1_SCL{slash}TIM4_CH1-Pad58)") (class "Default")
      (node (ref "U1") (pin "58") (pinfunction "PB6/I2C1_SCL/TIM4_CH1_58") (pintype "passive"))
    )
    (net (code "59") (name "unconnected-(U1-PB7{slash}I2C1_SDA{slash}TIM4_CH2-Pad59)") (class "Default")
      (node (ref "U1") (pin "59") (pinfunction "PB7/I2C1_SDA/TIM4_CH2_59") (pintype "passive"))
    )
    (net (code "60") (name "unconnected-(U1-PB8{slash}TIM4_CH3{slash}SDIO_D4-Pad61)") (class "Default")
      (node (ref "U1") (pin "61") (pinfunction "PB8/TIM4_CH3/SDIO_D4_61") (pintype "passive"))
    )
    (net (code "61") (name "unconnected-(U1-PB9{slash}TIM4_CH4{slash}SDIO_D5-Pad62)") (class "Default")
      (node (ref "U1") (pin "62") (pinfunction "PB9/TIM4_CH4/SDIO_D5_62") (pintype "passive"))
    )
    (net (code "62") (name "unconnected-(U1-PB10{slash}I2C2_SCL{slash}U3_TX-Pad29)") (class "Default")
      (node (ref "U1") (pin "29") (pinfunction "PB10/I2C2_SCL/U3_TX_29") (pintype "passive"))
    )
    (net (code "63") (name "unconnected-(U1-PB11{slash}I2C2_SDA{slash}U3_RX-Pad30)") (class "Default")
      (node (ref "U1") (pin "30") (pinfunction "PB11/I2C2_SDA/U3_RX_30") (pintype "passive"))
    )
    (net (code "64") (name "unconnected-(U1-PC0{slash}ADC10-Pad8)") (class "Default")
      (node (ref "U1") (pin "8") (pinfunction "PC0/ADC10_8") (pintype "passive"))
    )
    (net (code "65") (name "unconnected-(U1-PC1{slash}ADC11-Pad9)") (class "Default")
      (node (ref "U1") (pin "9") (pinfunction "PC1/ADC11_9") (pintype "passive"))
    )
    (net (code "66") (name "unconnected-(U1-PC2{slash}ADC12-Pad10)") (class "Default")
      (node (ref "U1") (pin "10") (pinfunction "PC2/ADC12_10") (pintype "passive"))
    )
    (net (code "67") (name "unconnected-(U1-PC3{slash}ADC13-Pad11)") (class "Default")
      (node (ref "U1") (pin "11") (pinfunction "PC3/ADC13_11") (pintype "passive"))
    )
    (net (code "68") (name "unconnected-(U1-PC4{slash}ADC14-Pad24)") (class "Default")
      (node (ref "U1") (pin "24") (pinfunction "PC4/ADC14_24") (pintype "passive"))
    )
    (net (code "69") (name "unconnected-(U1-PC5{slash}ADC15-Pad25)") (class "Default")
      (node (ref "U1") (pin "25") (pinfunction "PC5/ADC15_25") (pintype "passive"))
    )
    (net (code "70") (name "unconnected-(U1-PC6{slash}I2S2_MCK{slash}TIM8_CH1{slash}SDIO_D6-Pad37)") (class "Default")
      (node (ref "U1") (pin "37") (pinfunction "PC6/I2S2_MCK/TIM8_CH1/SDIO_D6_37") (pintype "passive"))
    )
    (net (code "71") (name "unconnected-(U1-PC7{slash}I2S3_MCK{slash}TIM8_CH2{slash}SDIO_D7-Pad38)") (class "Default")
      (node (ref "U1") (pin "38") (pinfunction "PC7/I2S3_MCK/TIM8_CH2/SDIO_D7_38") (pintype "passive"))
    )
    (net (code "72") (name "unconnected-(U1-PC8{slash}TIM8_CH3{slash}SDIO_D0-Pad39)") (class "Default")
      (node (ref "U1") (pin "39") (pinfunction "PC8/TIM8_CH3/SDIO_D0_39") (pintype "passive"))
    )
    (net (code "73") (name "unconnected-(U1-PC10{slash}U4_TX{slash}SDIO_D2-Pad51)") (class "Default")
      (node (ref "U1") (pin "51") (pinfunction "PC10/U4_TX/SDIO_D2_51") (pintype "passive"))
    )
    (net (code "74") (name "unconnected-(U1-PC11{slash}U4_RX{slash}SDIO_D3-Pad52)") (class "Default")
      (node (ref "U1") (pin "52") (pinfunction "PC11/U4_RX/SDIO_D3_52") (pintype "passive"))
    )
    (net (code "75") (name "unconnected-(U1-PC13{slash}ANT1-Pad2)") (class "Default")
      (node (ref "U1") (pin "2") (pinfunction "PC13/ANT1_2") (pintype "passive"))
    )
    (net (code "76") (name "unconnected-(U1-PC14{slash}OSC32-Pad3)") (class "Default")
      (node (ref "U1") (pin "3") (pinfunction "PC14/OSC32_3") (pintype "passive"))
    )
    (net (code "77") (name "unconnected-(U1-PC15{slash}OSC32-Pad4)") (class "Default")
      (node (ref "U1") (pin "4") (pinfunction "PC15/OSC32_4") (pintype "passive"))
    )
    (net (code "78") (name "unconnected-(U1-PD2{slash}TIM3_ETR{slash}U5_RX{slash}SDIO_CMD-Pad54)") (class "Default")
      (node (ref "U1") (pin "54") (pinfunction "PD2/TIM3_ETR/U5_RX/SDIO_CMD_54") (pintype "passive"))
    )
    (net (code "79") (name "unconnected-(U3-NC-Pad4)") (class "Default")
      (node (ref "U3") (pin "4") (pinfunction "NC_4") (pintype "passive"))
    )
  )
)
